# Raspberry_Pi_Card_Connector.net
KiCad netlist of a schematic drawn in Altium Designer
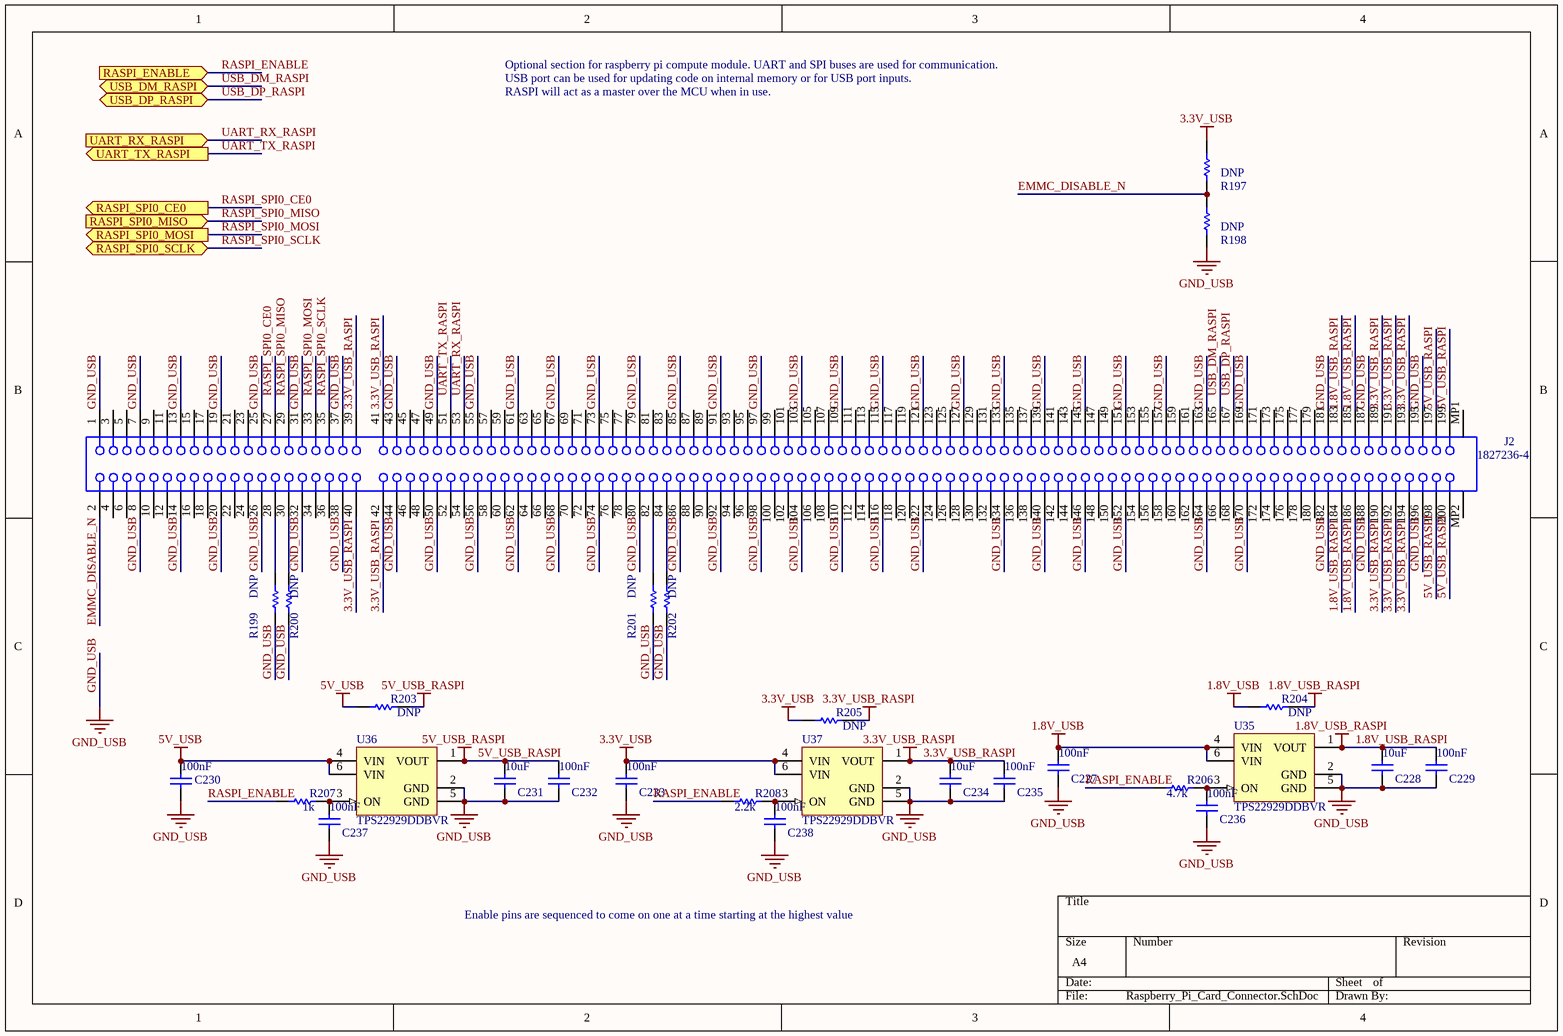
[diagram p0: Raspberry_Pi_Card_Connector.SchDoc]

(export (version "E")
  (design (tool "Eeschema 10.0.6"))
  (components
    (comp (ref "C227")
      (value "100nF")
      (footprint "CAPC0402(1005)60_L")
      (description "0402 (1005 Metric) Chip Capacitor")
      (fields (field (name "Comment") "CAP0402"))
      (libsource (lib "Altium Content Vault") (part "CMP-1590-00004-1"))
    )
    (comp (ref "C228")
      (value "10uF")
      (footprint "CAPC0805(2012)145_L")
      (description "0805 (2012 Metric) Chip Capacitor")
      (fields (field (name "Comment") "CAP0805"))
      (libsource (lib "Altium Content Vault") (part "CMP-1590-00003-1"))
    )
    (comp (ref "C229")
      (value "100nF")
      (footprint "CAPC0402(1005)60_L")
      (description "0402 (1005 Metric) Chip Capacitor")
      (fields (field (name "Comment") "CAP0402"))
      (libsource (lib "Altium Content Vault") (part "CMP-1590-00004-1"))
    )
    (comp (ref "C230")
      (value "100nF")
      (footprint "CAPC0402(1005)60_L")
      (description "0402 (1005 Metric) Chip Capacitor")
      (fields (field (name "Comment") "CAP0402"))
      (libsource (lib "Altium Content Vault") (part "CMP-1590-00004-1"))
    )
    (comp (ref "C231")
      (value "10uF")
      (footprint "CAPC0805(2012)145_L")
      (description "0805 (2012 Metric) Chip Capacitor")
      (fields (field (name "Comment") "CAP0805"))
      (libsource (lib "Altium Content Vault") (part "CMP-1590-00003-1"))
    )
    (comp (ref "C232")
      (value "100nF")
      (footprint "CAPC0402(1005)60_L")
      (description "0402 (1005 Metric) Chip Capacitor")
      (fields (field (name "Comment") "CAP0402"))
      (libsource (lib "Altium Content Vault") (part "CMP-1590-00004-1"))
    )
    (comp (ref "C233")
      (value "100nF")
      (footprint "CAPC0402(1005)60_L")
      (description "0402 (1005 Metric) Chip Capacitor")
      (fields (field (name "Comment") "CAP0402"))
      (libsource (lib "Altium Content Vault") (part "CMP-1590-00004-1"))
    )
    (comp (ref "C234")
      (value "10uF")
      (footprint "CAPC0805(2012)145_L")
      (description "0805 (2012 Metric) Chip Capacitor")
      (fields (field (name "Comment") "CAP0805"))
      (libsource (lib "Altium Content Vault") (part "CMP-1590-00003-1"))
    )
    (comp (ref "C235")
      (value "100nF")
      (footprint "CAPC0402(1005)60_L")
      (description "0402 (1005 Metric) Chip Capacitor")
      (fields (field (name "Comment") "CAP0402"))
      (libsource (lib "Altium Content Vault") (part "CMP-1590-00004-1"))
    )
    (comp (ref "C236")
      (value "100nF")
      (footprint "CAPC0402(1005)60_L")
      (description "0402 (1005 Metric) Chip Capacitor")
      (fields (field (name "Comment") "CAP0402"))
      (libsource (lib "Altium Content Vault") (part "CMP-1590-00004-1"))
    )
    (comp (ref "C237")
      (value "100nF")
      (footprint "CAPC0402(1005)60_L")
      (description "0402 (1005 Metric) Chip Capacitor")
      (fields (field (name "Comment") "CAP0402"))
      (libsource (lib "Altium Content Vault") (part "CMP-1590-00004-1"))
    )
    (comp (ref "C238")
      (value "100nF")
      (footprint "CAPC0402(1005)60_L")
      (description "0402 (1005 Metric) Chip Capacitor")
      (fields (field (name "Comment") "CAP0402"))
      (libsource (lib "Altium Content Vault") (part "CMP-1590-00004-1"))
    )
    (comp (ref "J2")
      (value "1827236-4")
      (footprint "BTB-SM0-6-2V200")
      (description "Board-to-Board Connector, SMT, Right Angle, Pitch 0.6mm, Voltage Key 1.8V, 200-Position")
      (fields (field (name "PUBLISHER") "Altium"))
      (libsource (lib "Altium Content Vault") (part "CN-2S-F-R200"))
    )
    (comp (ref "R197")
      (value "DNP")
      (footprint "RESC0402(1005)_L")
      (description "0402 (1005 Metric) Chip Resistor")
      (fields (field (name "Comment") "RES0402"))
      (libsource (lib "Altium Content Vault") (part "CMP-1591-00004-1"))
    )
    (comp (ref "R198")
      (value "DNP")
      (footprint "RESC0402(1005)_L")
      (description "0402 (1005 Metric) Chip Resistor")
      (fields (field (name "Comment") "RES0402"))
      (libsource (lib "Altium Content Vault") (part "CMP-1591-00004-1"))
    )
    (comp (ref "R199")
      (value "DNP")
      (footprint "RESC0402(1005)_L")
      (description "0402 (1005 Metric) Chip Resistor")
      (fields (field (name "Comment") "RES0402"))
      (libsource (lib "Altium Content Vault") (part "CMP-1591-00004-1"))
    )
    (comp (ref "R200")
      (value "DNP")
      (footprint "RESC0402(1005)_L")
      (description "0402 (1005 Metric) Chip Resistor")
      (fields (field (name "Comment") "RES0402"))
      (libsource (lib "Altium Content Vault") (part "CMP-1591-00004-1"))
    )
    (comp (ref "R201")
      (value "DNP")
      (footprint "RESC0402(1005)_L")
      (description "0402 (1005 Metric) Chip Resistor")
      (fields (field (name "Comment") "RES0402"))
      (libsource (lib "Altium Content Vault") (part "CMP-1591-00004-1"))
    )
    (comp (ref "R202")
      (value "DNP")
      (footprint "RESC0402(1005)_L")
      (description "0402 (1005 Metric) Chip Resistor")
      (fields (field (name "Comment") "RES0402"))
      (libsource (lib "Altium Content Vault") (part "CMP-1591-00004-1"))
    )
    (comp (ref "R203")
      (value "DNP")
      (footprint "RESC0402(1005)_L")
      (description "0402 (1005 Metric) Chip Resistor")
      (fields (field (name "Comment") "RES0402"))
      (libsource (lib "Altium Content Vault") (part "CMP-1591-00004-1"))
    )
    (comp (ref "R204")
      (value "DNP")
      (footprint "RESC0402(1005)_L")
      (description "0402 (1005 Metric) Chip Resistor")
      (fields (field (name "Comment") "RES0402"))
      (libsource (lib "Altium Content Vault") (part "CMP-1591-00004-1"))
    )
    (comp (ref "R205")
      (value "DNP")
      (footprint "RESC0402(1005)_L")
      (description "0402 (1005 Metric) Chip Resistor")
      (fields (field (name "Comment") "RES0402"))
      (libsource (lib "Altium Content Vault") (part "CMP-1591-00004-1"))
    )
    (comp (ref "R206")
      (value "4.7k")
      (footprint "RESC0402(1005)_L")
      (description "0402 (1005 Metric) Chip Resistor")
      (fields (field (name "Comment") "RES0402"))
      (libsource (lib "Altium Content Vault") (part "CMP-1591-00004-1"))
    )
    (comp (ref "R207")
      (value "1k")
      (footprint "RESC0402(1005)_L")
      (description "0402 (1005 Metric) Chip Resistor")
      (fields (field (name "Comment") "RES0402"))
      (libsource (lib "Altium Content Vault") (part "CMP-1591-00004-1"))
    )
    (comp (ref "R208")
      (value "2.2k")
      (footprint "RESC0402(1005)_L")
      (description "0402 (1005 Metric) Chip Resistor")
      (fields (field (name "Comment") "RES0402"))
      (libsource (lib "Altium Content Vault") (part "CMP-1591-00004-1"))
    )
    (comp (ref "U35")
      (value "TPS22929DDBVR")
      (footprint "DBV6_N")
      (fields (field (name "MANUFACTURER") "Texas Instruments"))
      (libsource (lib "Altium Content Vault") (part "TI-TPS22929DDBV6"))
    )
    (comp (ref "U36")
      (value "TPS22929DDBVR")
      (footprint "DBV6_N")
      (fields (field (name "MANUFACTURER") "Texas Instruments"))
      (libsource (lib "Altium Content Vault") (part "TI-TPS22929DDBV6"))
    )
    (comp (ref "U37")
      (value "TPS22929DDBVR")
      (footprint "DBV6_N")
      (fields (field (name "MANUFACTURER") "Texas Instruments"))
      (libsource (lib "Altium Content Vault") (part "TI-TPS22929DDBV6"))
    )
  )
  (nets
    (net (code "1") (name "/EMMC_DISABLE_N") (class "Default")
      (node (ref "J2") (pin "2") (pinfunction "2_2") (pintype "passive"))
      (node (ref "R197") (pin "2") (pinfunction "2_2") (pintype "passive"))
      (node (ref "R198") (pin "1") (pinfunction "1_1") (pintype "passive"))
    )
    (net (code "2") (name "/RASPI_ENABLE") (class "Default")
      (node (ref "R206") (pin "2") (pinfunction "2_2") (pintype "passive"))
      (node (ref "R207") (pin "2") (pinfunction "2_2") (pintype "passive"))
      (node (ref "R208") (pin "2") (pinfunction "2_2") (pintype "passive"))
    )
    (net (code "3") (name "/RASPI_SPI0_CE0") (class "Default")
      (node (ref "J2") (pin "27") (pinfunction "27_27") (pintype "passive"))
    )
    (net (code "4") (name "/RASPI_SPI0_MISO") (class "Default")
      (node (ref "J2") (pin "29") (pinfunction "29_29") (pintype "passive"))
    )
    (net (code "5") (name "/RASPI_SPI0_MOSI") (class "Default")
      (node (ref "J2") (pin "33") (pinfunction "33_33") (pintype "passive"))
    )
    (net (code "6") (name "/RASPI_SPI0_SCLK") (class "Default")
      (node (ref "J2") (pin "35") (pinfunction "35_35") (pintype "passive"))
    )
    (net (code "7") (name "/UART_RX_RASPI") (class "Default")
      (node (ref "J2") (pin "53") (pinfunction "53_53") (pintype "passive"))
    )
    (net (code "8") (name "/UART_TX_RASPI") (class "Default")
      (node (ref "J2") (pin "51") (pinfunction "51_51") (pintype "passive"))
    )
    (net (code "9") (name "/USB_DM_RASPI") (class "Default")
      (node (ref "J2") (pin "165") (pinfunction "165_165") (pintype "passive"))
    )
    (net (code "10") (name "/USB_DP_RASPI") (class "Default")
      (node (ref "J2") (pin "167") (pinfunction "167_167") (pintype "passive"))
    )
    (net (code "11") (name "1.8V_USB") (class "Default")
      (node (ref "C227") (pin "1") (pinfunction "1_1") (pintype "passive"))
      (node (ref "R204") (pin "2") (pinfunction "2_2") (pintype "passive"))
      (node (ref "U35") (pin "4") (pinfunction "VIN_4") (pintype "power_in"))
      (node (ref "U35") (pin "6") (pinfunction "VIN_6") (pintype "power_in"))
    )
    (net (code "12") (name "1.8V_USB_RASPI") (class "Default")
      (node (ref "C228") (pin "2") (pinfunction "2_2") (pintype "passive"))
      (node (ref "C229") (pin "1") (pinfunction "1_1") (pintype "passive"))
      (node (ref "J2") (pin "183") (pinfunction "183_183") (pintype "passive"))
      (node (ref "J2") (pin "184") (pinfunction "184_184") (pintype "passive"))
      (node (ref "J2") (pin "185") (pinfunction "185_185") (pintype "passive"))
      (node (ref "J2") (pin "186") (pinfunction "186_186") (pintype "passive"))
      (node (ref "R204") (pin "1") (pinfunction "1_1") (pintype "passive"))
      (node (ref "U35") (pin "1") (pinfunction "VOUT_1") (pintype "power_in"))
    )
    (net (code "13") (name "3.3V_USB") (class "Default")
      (node (ref "C233") (pin "1") (pinfunction "1_1") (pintype "passive"))
      (node (ref "R197") (pin "1") (pinfunction "1_1") (pintype "passive"))
      (node (ref "R205") (pin "2") (pinfunction "2_2") (pintype "passive"))
      (node (ref "U37") (pin "4") (pinfunction "VIN_4") (pintype "power_in"))
      (node (ref "U37") (pin "6") (pinfunction "VIN_6") (pintype "power_in"))
    )
    (net (code "14") (name "3.3V_USB_RASPI") (class "Default")
      (node (ref "C234") (pin "2") (pinfunction "2_2") (pintype "passive"))
      (node (ref "C235") (pin "1") (pinfunction "1_1") (pintype "passive"))
      (node (ref "J2") (pin "189") (pinfunction "189_189") (pintype "passive"))
      (node (ref "J2") (pin "190") (pinfunction "190_190") (pintype "passive"))
      (node (ref "J2") (pin "191") (pinfunction "191_191") (pintype "passive"))
      (node (ref "J2") (pin "192") (pinfunction "192_192") (pintype "passive"))
      (node (ref "J2") (pin "193") (pinfunction "193_193") (pintype "passive"))
      (node (ref "J2") (pin "194") (pinfunction "194_194") (pintype "passive"))
      (node (ref "J2") (pin "39") (pinfunction "39_39") (pintype "passive"))
      (node (ref "J2") (pin "40") (pinfunction "40_40") (pintype "passive"))
      (node (ref "J2") (pin "41") (pinfunction "41_41") (pintype "passive"))
      (node (ref "J2") (pin "42") (pinfunction "42_42") (pintype "passive"))
      (node (ref "R205") (pin "1") (pinfunction "1_1") (pintype "passive"))
      (node (ref "U37") (pin "1") (pinfunction "VOUT_1") (pintype "power_in"))
    )
    (net (code "15") (name "5V_USB") (class "Default")
      (node (ref "C230") (pin "1") (pinfunction "1_1") (pintype "passive"))
      (node (ref "R203") (pin "2") (pinfunction "2_2") (pintype "passive"))
      (node (ref "U36") (pin "4") (pinfunction "VIN_4") (pintype "power_in"))
      (node (ref "U36") (pin "6") (pinfunction "VIN_6") (pintype "power_in"))
    )
    (net (code "16") (name "5V_USB_RASPI") (class "Default")
      (node (ref "C231") (pin "2") (pinfunction "2_2") (pintype "passive"))
      (node (ref "C232") (pin "1") (pinfunction "1_1") (pintype "passive"))
      (node (ref "J2") (pin "197") (pinfunction "197_197") (pintype "passive"))
      (node (ref "J2") (pin "198") (pinfunction "198_198") (pintype "passive"))
      (node (ref "J2") (pin "199") (pinfunction "199_199") (pintype "passive"))
      (node (ref "J2") (pin "200") (pinfunction "200_200") (pintype "passive"))
      (node (ref "R203") (pin "1") (pinfunction "1_1") (pintype "passive"))
      (node (ref "U36") (pin "1") (pinfunction "VOUT_1") (pintype "power_in"))
    )
    (net (code "17") (name "GND_USB") (class "Default")
      (node (ref "C227") (pin "2") (pinfunction "2_2") (pintype "passive"))
      (node (ref "C228") (pin "1") (pinfunction "1_1") (pintype "passive"))
      (node (ref "C229") (pin "2") (pinfunction "2_2") (pintype "passive"))
      (node (ref "C230") (pin "2") (pinfunction "2_2") (pintype "passive"))
      (node (ref "C231") (pin "1") (pinfunction "1_1") (pintype "passive"))
      (node (ref "C232") (pin "2") (pinfunction "2_2") (pintype "passive"))
      (node (ref "C233") (pin "2") (pinfunction "2_2") (pintype "passive"))
      (node (ref "C234") (pin "1") (pinfunction "1_1") (pintype "passive"))
      (node (ref "C235") (pin "2") (pinfunction "2_2") (pintype "passive"))
      (node (ref "C236") (pin "2") (pinfunction "2_2") (pintype "passive"))
      (node (ref "C237") (pin "2") (pinfunction "2_2") (pintype "passive"))
      (node (ref "C238") (pin "2") (pinfunction "2_2") (pintype "passive"))
      (node (ref "J2") (pin "1") (pinfunction "1_1") (pintype "passive"))
      (node (ref "J2") (pin "103") (pinfunction "103_103") (pintype "passive"))
      (node (ref "J2") (pin "104") (pinfunction "104_104") (pintype "passive"))
      (node (ref "J2") (pin "109") (pinfunction "109_109") (pintype "passive"))
      (node (ref "J2") (pin "110") (pinfunction "110_110") (pintype "passive"))
      (node (ref "J2") (pin "115") (pinfunction "115_115") (pintype "passive"))
      (node (ref "J2") (pin "116") (pinfunction "116_116") (pintype "passive"))
      (node (ref "J2") (pin "121") (pinfunction "121_121") (pintype "passive"))
      (node (ref "J2") (pin "122") (pinfunction "122_122") (pintype "passive"))
      (node (ref "J2") (pin "127") (pinfunction "127_127") (pintype "passive"))
      (node (ref "J2") (pin "13") (pinfunction "13_13") (pintype "passive"))
      (node (ref "J2") (pin "133") (pinfunction "133_133") (pintype "passive"))
      (node (ref "J2") (pin "134") (pinfunction "134_134") (pintype "passive"))
      (node (ref "J2") (pin "139") (pinfunction "139_139") (pintype "passive"))
      (node (ref "J2") (pin "14") (pinfunction "14_14") (pintype "passive"))
      (node (ref "J2") (pin "140") (pinfunction "140_140") (pintype "passive"))
      (node (ref "J2") (pin "145") (pinfunction "145_145") (pintype "passive"))
      (node (ref "J2") (pin "146") (pinfunction "146_146") (pintype "passive"))
      (node (ref "J2") (pin "151") (pinfunction "151_151") (pintype "passive"))
      (node (ref "J2") (pin "152") (pinfunction "152_152") (pintype "passive"))
      (node (ref "J2") (pin "157") (pinfunction "157_157") (pintype "passive"))
      (node (ref "J2") (pin "163") (pinfunction "163_163") (pintype "passive"))
      (node (ref "J2") (pin "164") (pinfunction "164_164") (pintype "passive"))
      (node (ref "J2") (pin "169") (pinfunction "169_169") (pintype "passive"))
      (node (ref "J2") (pin "170") (pinfunction "170_170") (pintype "passive"))
      (node (ref "J2") (pin "181") (pinfunction "181_181") (pintype "passive"))
      (node (ref "J2") (pin "182") (pinfunction "182_182") (pintype "passive"))
      (node (ref "J2") (pin "187") (pinfunction "187_187") (pintype "passive"))
      (node (ref "J2") (pin "188") (pinfunction "188_188") (pintype "passive"))
      (node (ref "J2") (pin "19") (pinfunction "19_19") (pintype "passive"))
      (node (ref "J2") (pin "195") (pinfunction "195_195") (pintype "passive"))
      (node (ref "J2") (pin "196") (pinfunction "196_196") (pintype "passive"))
      (node (ref "J2") (pin "20") (pinfunction "20_20") (pintype "passive"))
      (node (ref "J2") (pin "25") (pinfunction "25_25") (pintype "passive"))
      (node (ref "J2") (pin "26") (pinfunction "26_26") (pintype "passive"))
      (node (ref "J2") (pin "31") (pinfunction "31_31") (pintype "passive"))
      (node (ref "J2") (pin "32") (pinfunction "32_32") (pintype "passive"))
      (node (ref "J2") (pin "37") (pinfunction "37_37") (pintype "passive"))
      (node (ref "J2") (pin "38") (pinfunction "38_38") (pintype "passive"))
      (node (ref "J2") (pin "43") (pinfunction "43_43") (pintype "passive"))
      (node (ref "J2") (pin "44") (pinfunction "44_44") (pintype "passive"))
      (node (ref "J2") (pin "49") (pinfunction "49_49") (pintype "passive"))
      (node (ref "J2") (pin "50") (pinfunction "50_50") (pintype "passive"))
      (node (ref "J2") (pin "55") (pinfunction "55_55") (pintype "passive"))
      (node (ref "J2") (pin "56") (pinfunction "56_56") (pintype "passive"))
      (node (ref "J2") (pin "61") (pinfunction "61_61") (pintype "passive"))
      (node (ref "J2") (pin "62") (pinfunction "62_62") (pintype "passive"))
      (node (ref "J2") (pin "67") (pinfunction "67_67") (pintype "passive"))
      (node (ref "J2") (pin "68") (pinfunction "68_68") (pintype "passive"))
      (node (ref "J2") (pin "7") (pinfunction "7_7") (pintype "passive"))
      (node (ref "J2") (pin "73") (pinfunction "73_73") (pintype "passive"))
      (node (ref "J2") (pin "74") (pinfunction "74_74") (pintype "passive"))
      (node (ref "J2") (pin "79") (pinfunction "79_79") (pintype "passive"))
      (node (ref "J2") (pin "8") (pinfunction "8_8") (pintype "passive"))
      (node (ref "J2") (pin "80") (pinfunction "80_80") (pintype "passive"))
      (node (ref "J2") (pin "85") (pinfunction "85_85") (pintype "passive"))
      (node (ref "J2") (pin "86") (pinfunction "86_86") (pintype "passive"))
      (node (ref "J2") (pin "91") (pinfunction "91_91") (pintype "passive"))
      (node (ref "J2") (pin "92") (pinfunction "92_92") (pintype "passive"))
      (node (ref "J2") (pin "97") (pinfunction "97_97") (pintype "passive"))
      (node (ref "J2") (pin "98") (pinfunction "98_98") (pintype "passive"))
      (node (ref "R198") (pin "2") (pinfunction "2_2") (pintype "passive"))
      (node (ref "R199") (pin "2") (pinfunction "2_2") (pintype "passive"))
      (node (ref "R200") (pin "2") (pinfunction "2_2") (pintype "passive"))
      (node (ref "R201") (pin "2") (pinfunction "2_2") (pintype "passive"))
      (node (ref "R202") (pin "2") (pinfunction "2_2") (pintype "passive"))
      (node (ref "U35") (pin "2") (pinfunction "GND_2") (pintype "power_in"))
      (node (ref "U35") (pin "5") (pinfunction "GND_5") (pintype "power_in"))
      (node (ref "U36") (pin "2") (pinfunction "GND_2") (pintype "power_in"))
      (node (ref "U36") (pin "5") (pinfunction "GND_5") (pintype "power_in"))
      (node (ref "U37") (pin "2") (pinfunction "GND_2") (pintype "power_in"))
      (node (ref "U37") (pin "5") (pinfunction "GND_5") (pintype "power_in"))
    )
    (net (code "18") (name "Net-(J2-Pad28)") (class "Default")
      (node (ref "J2") (pin "28") (pinfunction "28_28") (pintype "passive"))
      (node (ref "R199") (pin "1") (pinfunction "1_1") (pintype "passive"))
    )
    (net (code "19") (name "Net-(J2-Pad30)") (class "Default")
      (node (ref "J2") (pin "30") (pinfunction "30_30") (pintype "passive"))
      (node (ref "R200") (pin "1") (pinfunction "1_1") (pintype "passive"))
    )
    (net (code "20") (name "Net-(J2-Pad82)") (class "Default")
      (node (ref "J2") (pin "82") (pinfunction "82_82") (pintype "passive"))
      (node (ref "R202") (pin "1") (pinfunction "1_1") (pintype "passive"))
    )
    (net (code "21") (name "Net-(J2-Pad84)") (class "Default")
      (node (ref "J2") (pin "84") (pinfunction "84_84") (pintype "passive"))
      (node (ref "R201") (pin "1") (pinfunction "1_1") (pintype "passive"))
    )
    (net (code "22") (name "Net-(U35-ON)") (class "Default")
      (node (ref "C236") (pin "1") (pinfunction "1_1") (pintype "passive"))
      (node (ref "R206") (pin "1") (pinfunction "1_1") (pintype "passive"))
      (node (ref "U35") (pin "3") (pinfunction "ON_3") (pintype "input"))
    )
    (net (code "23") (name "Net-(U36-ON)") (class "Default")
      (node (ref "C237") (pin "1") (pinfunction "1_1") (pintype "passive"))
      (node (ref "R207") (pin "1") (pinfunction "1_1") (pintype "passive"))
      (node (ref "U36") (pin "3") (pinfunction "ON_3") (pintype "input"))
    )
    (net (code "24") (name "Net-(U37-ON)") (class "Default")
      (node (ref "C238") (pin "1") (pinfunction "1_1") (pintype "passive"))
      (node (ref "R208") (pin "1") (pinfunction "1_1") (pintype "passive"))
      (node (ref "U37") (pin "3") (pinfunction "ON_3") (pintype "input"))
    )
    (net (code "25") (name "unconnected-(J2-Pad3)") (class "Default")
      (node (ref "J2") (pin "3") (pinfunction "3_3") (pintype "passive"))
    )
    (net (code "26") (name "unconnected-(J2-Pad4)") (class "Default")
      (node (ref "J2") (pin "4") (pinfunction "4_4") (pintype "passive"))
    )
    (net (code "27") (name "unconnected-(J2-Pad5)") (class "Default")
      (node (ref "J2") (pin "5") (pinfunction "5_5") (pintype "passive"))
    )
    (net (code "28") (name "unconnected-(J2-Pad6)") (class "Default")
      (node (ref "J2") (pin "6") (pinfunction "6_6") (pintype "passive"))
    )
    (net (code "29") (name "unconnected-(J2-Pad9)") (class "Default")
      (node (ref "J2") (pin "9") (pinfunction "9_9") (pintype "passive"))
    )
    (net (code "30") (name "unconnected-(J2-Pad10)") (class "Default")
      (node (ref "J2") (pin "10") (pinfunction "10_10") (pintype "passive"))
    )
    (net (code "31") (name "unconnected-(J2-Pad11)") (class "Default")
      (node (ref "J2") (pin "11") (pinfunction "11_11") (pintype "passive"))
    )
    (net (code "32") (name "unconnected-(J2-Pad12)") (class "Default")
      (node (ref "J2") (pin "12") (pinfunction "12_12") (pintype "passive"))
    )
    (net (code "33") (name "unconnected-(J2-Pad15)") (class "Default")
      (node (ref "J2") (pin "15") (pinfunction "15_15") (pintype "passive"))
    )
    (net (code "34") (name "unconnected-(J2-Pad16)") (class "Default")
      (node (ref "J2") (pin "16") (pinfunction "16_16") (pintype "passive"))
    )
    (net (code "35") (name "unconnected-(J2-Pad17)") (class "Default")
      (node (ref "J2") (pin "17") (pinfunction "17_17") (pintype "passive"))
    )
    (net (code "36") (name "unconnected-(J2-Pad18)") (class "Default")
      (node (ref "J2") (pin "18") (pinfunction "18_18") (pintype "passive"))
    )
    (net (code "37") (name "unconnected-(J2-Pad21)") (class "Default")
      (node (ref "J2") (pin "21") (pinfunction "21_21") (pintype "passive"))
    )
    (net (code "38") (name "unconnected-(J2-Pad22)") (class "Default")
      (node (ref "J2") (pin "22") (pinfunction "22_22") (pintype "passive"))
    )
    (net (code "39") (name "unconnected-(J2-Pad23)") (class "Default")
      (node (ref "J2") (pin "23") (pinfunction "23_23") (pintype "passive"))
    )
    (net (code "40") (name "unconnected-(J2-Pad24)") (class "Default")
      (node (ref "J2") (pin "24") (pinfunction "24_24") (pintype "passive"))
    )
    (net (code "41") (name "unconnected-(J2-Pad34)") (class "Default")
      (node (ref "J2") (pin "34") (pinfunction "34_34") (pintype "passive"))
    )
    (net (code "42") (name "unconnected-(J2-Pad36)") (class "Default")
      (node (ref "J2") (pin "36") (pinfunction "36_36") (pintype "passive"))
    )
    (net (code "43") (name "unconnected-(J2-Pad45)") (class "Default")
      (node (ref "J2") (pin "45") (pinfunction "45_45") (pintype "passive"))
    )
    (net (code "44") (name "unconnected-(J2-Pad46)") (class "Default")
      (node (ref "J2") (pin "46") (pinfunction "46_46") (pintype "passive"))
    )
    (net (code "45") (name "unconnected-(J2-Pad47)") (class "Default")
      (node (ref "J2") (pin "47") (pinfunction "47_47") (pintype "passive"))
    )
    (net (code "46") (name "unconnected-(J2-Pad48)") (class "Default")
      (node (ref "J2") (pin "48") (pinfunction "48_48") (pintype "passive"))
    )
    (net (code "47") (name "unconnected-(J2-Pad52)") (class "Default")
      (node (ref "J2") (pin "52") (pinfunction "52_52") (pintype "passive"))
    )
    (net (code "48") (name "unconnected-(J2-Pad54)") (class "Default")
      (node (ref "J2") (pin "54") (pinfunction "54_54") (pintype "passive"))
    )
    (net (code "49") (name "unconnected-(J2-Pad57)") (class "Default")
      (node (ref "J2") (pin "57") (pinfunction "57_57") (pintype "passive"))
    )
    (net (code "50") (name "unconnected-(J2-Pad58)") (class "Default")
      (node (ref "J2") (pin "58") (pinfunction "58_58") (pintype "passive"))
    )
    (net (code "51") (name "unconnected-(J2-Pad59)") (class "Default")
      (node (ref "J2") (pin "59") (pinfunction "59_59") (pintype "passive"))
    )
    (net (code "52") (name "unconnected-(J2-Pad60)") (class "Default")
      (node (ref "J2") (pin "60") (pinfunction "60_60") (pintype "passive"))
    )
    (net (code "53") (name "unconnected-(J2-Pad63)") (class "Default")
      (node (ref "J2") (pin "63") (pinfunction "63_63") (pintype "passive"))
    )
    (net (code "54") (name "unconnected-(J2-Pad64)") (class "Default")
      (node (ref "J2") (pin "64") (pinfunction "64_64") (pintype "passive"))
    )
    (net (code "55") (name "unconnected-(J2-Pad65)") (class "Default")
      (node (ref "J2") (pin "65") (pinfunction "65_65") (pintype "passive"))
    )
    (net (code "56") (name "unconnected-(J2-Pad66)") (class "Default")
      (node (ref "J2") (pin "66") (pinfunction "66_66") (pintype "passive"))
    )
    (net (code "57") (name "unconnected-(J2-Pad69)") (class "Default")
      (node (ref "J2") (pin "69") (pinfunction "69_69") (pintype "passive"))
    )
    (net (code "58") (name "unconnected-(J2-Pad70)") (class "Default")
      (node (ref "J2") (pin "70") (pinfunction "70_70") (pintype "passive"))
    )
    (net (code "59") (name "unconnected-(J2-Pad71)") (class "Default")
      (node (ref "J2") (pin "71") (pinfunction "71_71") (pintype "passive"))
    )
    (net (code "60") (name "unconnected-(J2-Pad72)") (class "Default")
      (node (ref "J2") (pin "72") (pinfunction "72_72") (pintype "passive"))
    )
    (net (code "61") (name "unconnected-(J2-Pad75)") (class "Default")
      (node (ref "J2") (pin "75") (pinfunction "75_75") (pintype "passive"))
    )
    (net (code "62") (name "unconnected-(J2-Pad76)") (class "Default")
      (node (ref "J2") (pin "76") (pinfunction "76_76") (pintype "passive"))
    )
    (net (code "63") (name "unconnected-(J2-Pad77)") (class "Default")
      (node (ref "J2") (pin "77") (pinfunction "77_77") (pintype "passive"))
    )
    (net (code "64") (name "unconnected-(J2-Pad78)") (class "Default")
      (node (ref "J2") (pin "78") (pinfunction "78_78") (pintype "passive"))
    )
    (net (code "65") (name "unconnected-(J2-Pad81)") (class "Default")
      (node (ref "J2") (pin "81") (pinfunction "81_81") (pintype "passive"))
    )
    (net (code "66") (name "unconnected-(J2-Pad83)") (class "Default")
      (node (ref "J2") (pin "83") (pinfunction "83_83") (pintype "passive"))
    )
    (net (code "67") (name "unconnected-(J2-Pad87)") (class "Default")
      (node (ref "J2") (pin "87") (pinfunction "87_87") (pintype "passive"))
    )
    (net (code "68") (name "unconnected-(J2-Pad88)") (class "Default")
      (node (ref "J2") (pin "88") (pinfunction "88_88") (pintype "passive"))
    )
    (net (code "69") (name "unconnected-(J2-Pad89)") (class "Default")
      (node (ref "J2") (pin "89") (pinfunction "89_89") (pintype "passive"))
    )
    (net (code "70") (name "unconnected-(J2-Pad90)") (class "Default")
      (node (ref "J2") (pin "90") (pinfunction "90_90") (pintype "passive"))
    )
    (net (code "71") (name "unconnected-(J2-Pad93)") (class "Default")
      (node (ref "J2") (pin "93") (pinfunction "93_93") (pintype "passive"))
    )
    (net (code "72") (name "unconnected-(J2-Pad94)") (class "Default")
      (node (ref "J2") (pin "94") (pinfunction "94_94") (pintype "passive"))
    )
    (net (code "73") (name "unconnected-(J2-Pad95)") (class "Default")
      (node (ref "J2") (pin "95") (pinfunction "95_95") (pintype "passive"))
    )
    (net (code "74") (name "unconnected-(J2-Pad96)") (class "Default")
      (node (ref "J2") (pin "96") (pinfunction "96_96") (pintype "passive"))
    )
    (net (code "75") (name "unconnected-(J2-Pad99)") (class "Default")
      (node (ref "J2") (pin "99") (pinfunction "99_99") (pintype "passive"))
    )
    (net (code "76") (name "unconnected-(J2-Pad100)") (class "Default")
      (node (ref "J2") (pin "100") (pinfunction "100_100") (pintype "passive"))
    )
    (net (code "77") (name "unconnected-(J2-Pad101)") (class "Default")
      (node (ref "J2") (pin "101") (pinfunction "101_101") (pintype "passive"))
    )
    (net (code "78") (name "unconnected-(J2-Pad102)") (class "Default")
      (node (ref "J2") (pin "102") (pinfunction "102_102") (pintype "passive"))
    )
    (net (code "79") (name "unconnected-(J2-Pad105)") (class "Default")
      (node (ref "J2") (pin "105") (pinfunction "105_105") (pintype "passive"))
    )
    (net (code "80") (name "unconnected-(J2-Pad106)") (class "Default")
      (node (ref "J2") (pin "106") (pinfunction "106_106") (pintype "passive"))
    )
    (net (code "81") (name "unconnected-(J2-Pad107)") (class "Default")
      (node (ref "J2") (pin "107") (pinfunction "107_107") (pintype "passive"))
    )
    (net (code "82") (name "unconnected-(J2-Pad108)") (class "Default")
      (node (ref "J2") (pin "108") (pinfunction "108_108") (pintype "passive"))
    )
    (net (code "83") (name "unconnected-(J2-Pad111)") (class "Default")
      (node (ref "J2") (pin "111") (pinfunction "111_111") (pintype "passive"))
    )
    (net (code "84") (name "unconnected-(J2-Pad112)") (class "Default")
      (node (ref "J2") (pin "112") (pinfunction "112_112") (pintype "passive"))
    )
    (net (code "85") (name "unconnected-(J2-Pad113)") (class "Default")
      (node (ref "J2") (pin "113") (pinfunction "113_113") (pintype "passive"))
    )
    (net (code "86") (name "unconnected-(J2-Pad114)") (class "Default")
      (node (ref "J2") (pin "114") (pinfunction "114_114") (pintype "passive"))
    )
    (net (code "87") (name "unconnected-(J2-Pad117)") (class "Default")
      (node (ref "J2") (pin "117") (pinfunction "117_117") (pintype "passive"))
    )
    (net (code "88") (name "unconnected-(J2-Pad118)") (class "Default")
      (node (ref "J2") (pin "118") (pinfunction "118_118") (pintype "passive"))
    )
    (net (code "89") (name "unconnected-(J2-Pad119)") (class "Default")
      (node (ref "J2") (pin "119") (pinfunction "119_119") (pintype "passive"))
    )
    (net (code "90") (name "unconnected-(J2-Pad120)") (class "Default")
      (node (ref "J2") (pin "120") (pinfunction "120_120") (pintype "passive"))
    )
    (net (code "91") (name "unconnected-(J2-Pad123)") (class "Default")
      (node (ref "J2") (pin "123") (pinfunction "123_123") (pintype "passive"))
    )
    (net (code "92") (name "unconnected-(J2-Pad124)") (class "Default")
      (node (ref "J2") (pin "124") (pinfunction "124_124") (pintype "passive"))
    )
    (net (code "93") (name "unconnected-(J2-Pad125)") (class "Default")
      (node (ref "J2") (pin "125") (pinfunction "125_125") (pintype "passive"))
    )
    (net (code "94") (name "unconnected-(J2-Pad126)") (class "Default")
      (node (ref "J2") (pin "126") (pinfunction "126_126") (pintype "passive"))
    )
    (net (code "95") (name "unconnected-(J2-Pad128)") (class "Default")
      (node (ref "J2") (pin "128") (pinfunction "128_128") (pintype "passive"))
    )
    (net (code "96") (name "unconnected-(J2-Pad129)") (class "Default")
      (node (ref "J2") (pin "129") (pinfunction "129_129") (pintype "passive"))
    )
    (net (code "97") (name "unconnected-(J2-Pad130)") (class "Default")
      (node (ref "J2") (pin "130") (pinfunction "130_130") (pintype "passive"))
    )
    (net (code "98") (name "unconnected-(J2-Pad131)") (class "Default")
      (node (ref "J2") (pin "131") (pinfunction "131_131") (pintype "passive"))
    )
    (net (code "99") (name "unconnected-(J2-Pad132)") (class "Default")
      (node (ref "J2") (pin "132") (pinfunction "132_132") (pintype "passive"))
    )
    (net (code "100") (name "unconnected-(J2-Pad135)") (class "Default")
      (node (ref "J2") (pin "135") (pinfunction "135_135") (pintype "passive"))
    )
    (net (code "101") (name "unconnected-(J2-Pad136)") (class "Default")
      (node (ref "J2") (pin "136") (pinfunction "136_136") (pintype "passive"))
    )
    (net (code "102") (name "unconnected-(J2-Pad137)") (class "Default")
      (node (ref "J2") (pin "137") (pinfunction "137_137") (pintype "passive"))
    )
    (net (code "103") (name "unconnected-(J2-Pad138)") (class "Default")
      (node (ref "J2") (pin "138") (pinfunction "138_138") (pintype "passive"))
    )
    (net (code "104") (name "unconnected-(J2-Pad141)") (class "Default")
      (node (ref "J2") (pin "141") (pinfunction "141_141") (pintype "passive"))
    )
    (net (code "105") (name "unconnected-(J2-Pad142)") (class "Default")
      (node (ref "J2") (pin "142") (pinfunction "142_142") (pintype "passive"))
    )
    (net (code "106") (name "unconnected-(J2-Pad143)") (class "Default")
      (node (ref "J2") (pin "143") (pinfunction "143_143") (pintype "passive"))
    )
    (net (code "107") (name "unconnected-(J2-Pad144)") (class "Default")
      (node (ref "J2") (pin "144") (pinfunction "144_144") (pintype "passive"))
    )
    (net (code "108") (name "unconnected-(J2-Pad147)") (class "Default")
      (node (ref "J2") (pin "147") (pinfunction "147_147") (pintype "passive"))
    )
    (net (code "109") (name "unconnected-(J2-Pad148)") (class "Default")
      (node (ref "J2") (pin "148") (pinfunction "148_148") (pintype "passive"))
    )
    (net (code "110") (name "unconnected-(J2-Pad149)") (class "Default")
      (node (ref "J2") (pin "149") (pinfunction "149_149") (pintype "passive"))
    )
    (net (code "111") (name "unconnected-(J2-Pad150)") (class "Default")
      (node (ref "J2") (pin "150") (pinfunction "150_150") (pintype "passive"))
    )
    (net (code "112") (name "unconnected-(J2-Pad153)") (class "Default")
      (node (ref "J2") (pin "153") (pinfunction "153_153") (pintype "passive"))
    )
    (net (code "113") (name "unconnected-(J2-Pad154)") (class "Default")
      (node (ref "J2") (pin "154") (pinfunction "154_154") (pintype "passive"))
    )
    (net (code "114") (name "unconnected-(J2-Pad155)") (class "Default")
      (node (ref "J2") (pin "155") (pinfunction "155_155") (pintype "passive"))
    )
    (net (code "115") (name "unconnected-(J2-Pad156)") (class "Default")
      (node (ref "J2") (pin "156") (pinfunction "156_156") (pintype "passive"))
    )
    (net (code "116") (name "unconnected-(J2-Pad158)") (class "Default")
      (node (ref "J2") (pin "158") (pinfunction "158_158") (pintype "passive"))
    )
    (net (code "117") (name "unconnected-(J2-Pad159)") (class "Default")
      (node (ref "J2") (pin "159") (pinfunction "159_159") (pintype "passive"))
    )
    (net (code "118") (name "unconnected-(J2-Pad160)") (class "Default")
      (node (ref "J2") (pin "160") (pinfunction "160_160") (pintype "passive"))
    )
    (net (code "119") (name "unconnected-(J2-Pad161)") (class "Default")
      (node (ref "J2") (pin "161") (pinfunction "161_161") (pintype "passive"))
    )
    (net (code "120") (name "unconnected-(J2-Pad162)") (class "Default")
      (node (ref "J2") (pin "162") (pinfunction "162_162") (pintype "passive"))
    )
    (net (code "121") (name "unconnected-(J2-Pad166)") (class "Default")
      (node (ref "J2") (pin "166") (pinfunction "166_166") (pintype "passive"))
    )
    (net (code "122") (name "unconnected-(J2-Pad168)") (class "Default")
      (node (ref "J2") (pin "168") (pinfunction "168_168") (pintype "passive"))
    )
    (net (code "123") (name "unconnected-(J2-Pad171)") (class "Default")
      (node (ref "J2") (pin "171") (pinfunction "171_171") (pintype "passive"))
    )
    (net (code "124") (name "unconnected-(J2-Pad172)") (class "Default")
      (node (ref "J2") (pin "172") (pinfunction "172_172") (pintype "passive"))
    )
    (net (code "125") (name "unconnected-(J2-Pad173)") (class "Default")
      (node (ref "J2") (pin "173") (pinfunction "173_173") (pintype "passive"))
    )
    (net (code "126") (name "unconnected-(J2-Pad174)") (class "Default")
      (node (ref "J2") (pin "174") (pinfunction "174_174") (pintype "passive"))
    )
    (net (code "127") (name "unconnected-(J2-Pad175)") (class "Default")
      (node (ref "J2") (pin "175") (pinfunction "175_175") (pintype "passive"))
    )
    (net (code "128") (name "unconnected-(J2-Pad176)") (class "Default")
      (node (ref "J2") (pin "176") (pinfunction "176_176") (pintype "passive"))
    )
    (net (code "129") (name "unconnected-(J2-Pad177)") (class "Default")
      (node (ref "J2") (pin "177") (pinfunction "177_177") (pintype "passive"))
    )
    (net (code "130") (name "unconnected-(J2-Pad178)") (class "Default")
      (node (ref "J2") (pin "178") (pinfunction "178_178") (pintype "passive"))
    )
    (net (code "131") (name "unconnected-(J2-Pad179)") (class "Default")
      (node (ref "J2") (pin "179") (pinfunction "179_179") (pintype "passive"))
    )
    (net (code "132") (name "unconnected-(J2-Pad180)") (class "Default")
      (node (ref "J2") (pin "180") (pinfunction "180_180") (pintype "passive"))
    )
    (net (code "133") (name "unconnected-(J2-PadMP1)") (class "Default")
      (node (ref "J2") (pin "MP1") (pinfunction "MP1_MP1") (pintype "passive"))
    )
    (net (code "134") (name "unconnected-(J2-PadMP2)") (class "Default")
      (node (ref "J2") (pin "MP2") (pinfunction "MP2_MP2") (pintype "passive"))
    )
  )
)
